# PeripheralExample.net
KiCad netlist of a schematic drawn in EAGLE
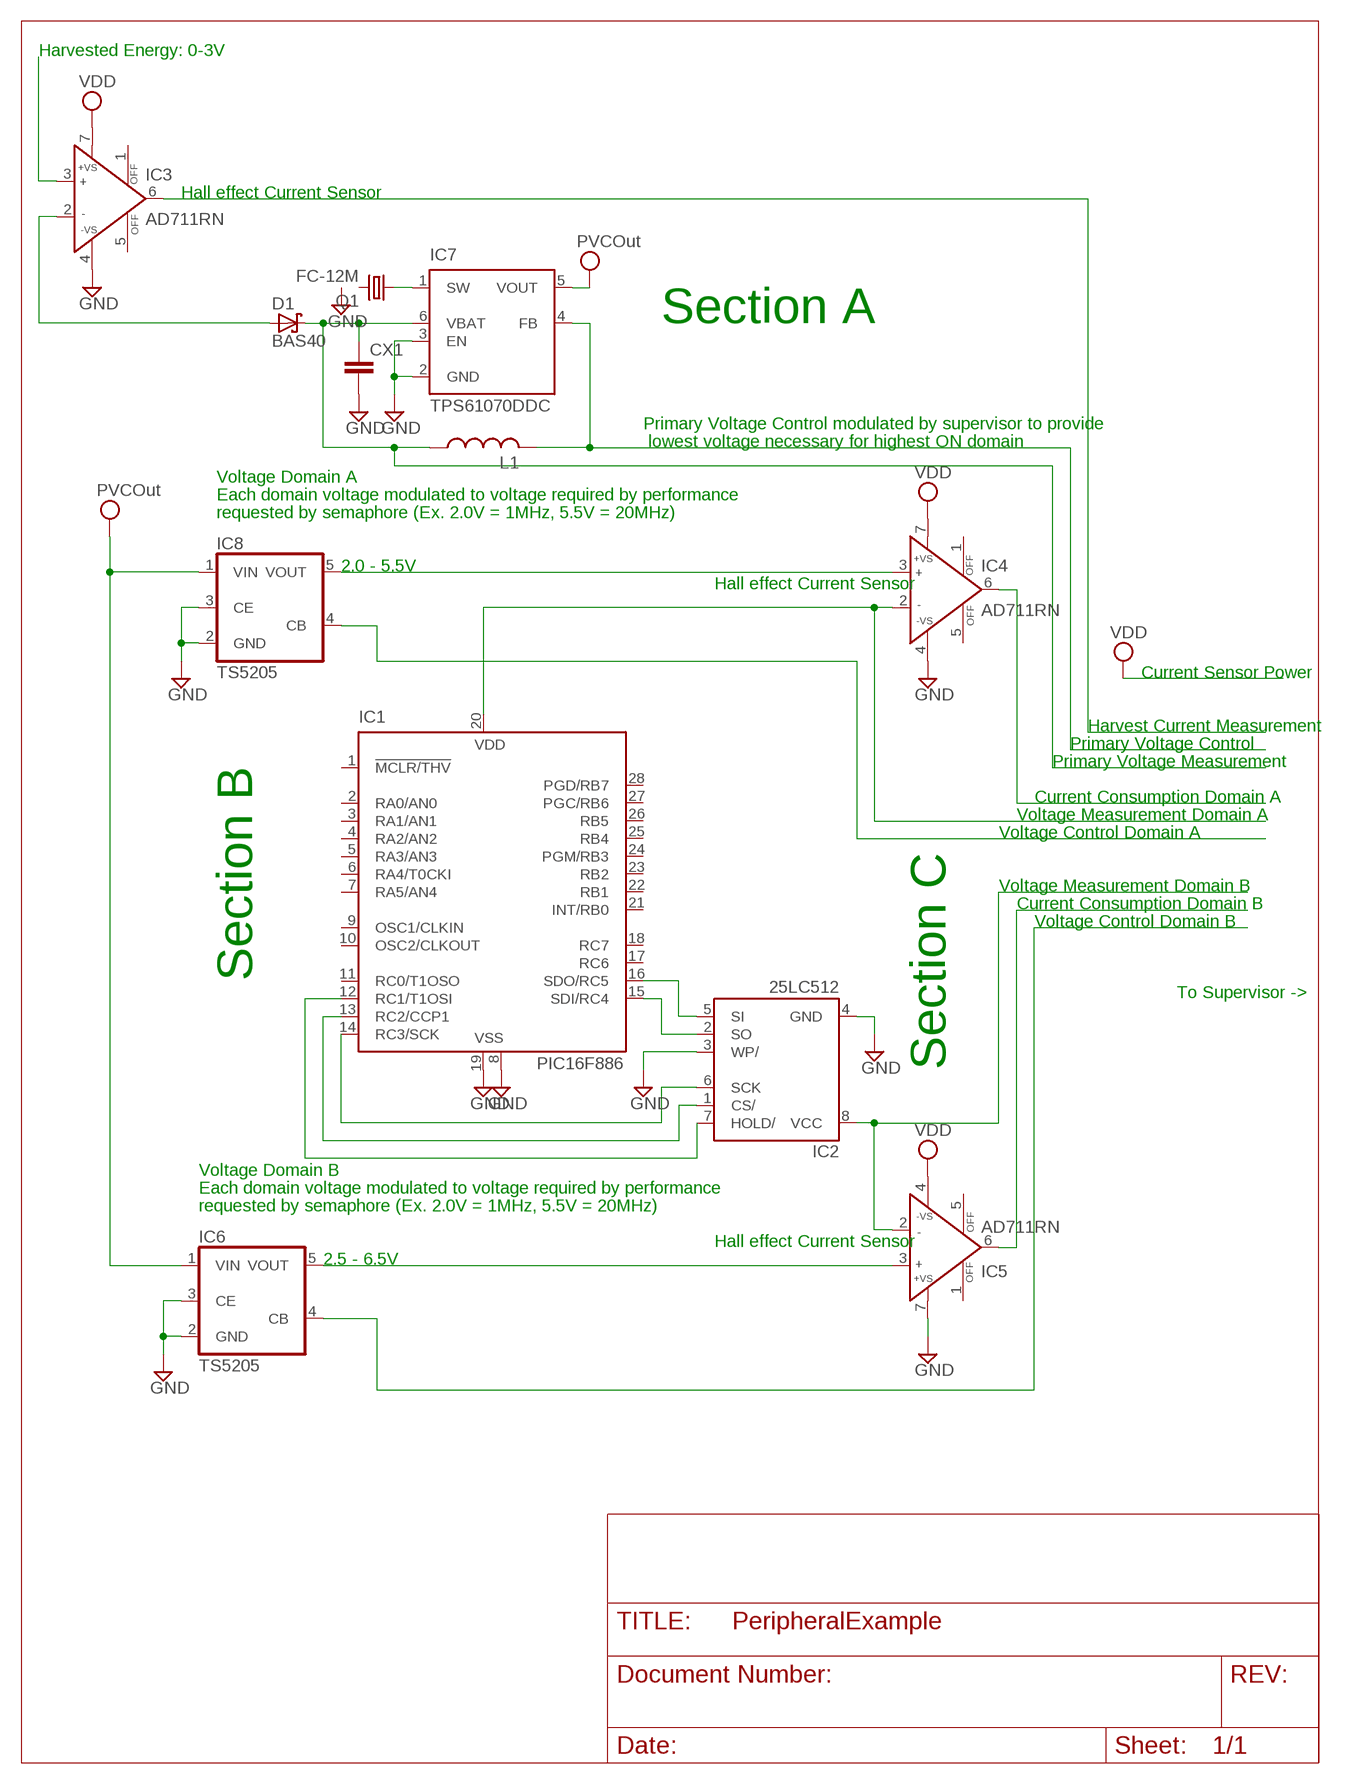
[diagram p0: schematic, sheet 1]

(export (version "E")
  (design (tool "Eeschema 10.0.6"))
  (components
    (comp (ref "CX1")
      (value "CXXC10B5")
      (footprint "eagle-import:XC10B5")
      (libsource (lib "eagle-import") (part "CXXC10B5"))
    )
    (comp (ref "D1")
      (value "BAS40")
      (footprint "eagle-import:SOT23")
      (libsource (lib "eagle-import") (part "BAS40"))
    )
    (comp (ref "IC1")
      (value "PIC16F886")
      (footprint "eagle-import:SO28W")
      (fields (field (name "MF") "MICROCHIP") (field (name "MPN") "PIC16F876-20/SO"))
      (libsource (lib "eagle-import") (part "PIC16876SOF"))
    )
    (comp (ref "IC2")
      (value "25LC512")
      (footprint "eagle-import:DIL08")
      (fields (field (name "MPN") "CAT25040LI-G"))
      (libsource (lib "eagle-import") (part "AT25P"))
    )
    (comp (ref "IC3")
      (value "AD711RN")
      (footprint "eagle-import:SO8")
      (fields (field (name "MF") "ALTERA CORPORATION") (field (name "MPN") "AD711KRZ"))
      (libsource (lib "eagle-import") (part "AD711RN"))
    )
    (comp (ref "IC4")
      (value "AD711RN")
      (footprint "eagle-import:SO8")
      (fields (field (name "MF") "ALTERA CORPORATION") (field (name "MPN") "AD711KRZ"))
      (libsource (lib "eagle-import") (part "AD711RN"))
    )
    (comp (ref "IC5")
      (value "AD711RN")
      (footprint "eagle-import:SO8")
      (fields (field (name "MF") "ALTERA CORPORATION") (field (name "MPN") "AD711KRZ"))
      (libsource (lib "eagle-import") (part "AD711RN"))
    )
    (comp (ref "IC6")
      (value "TS5205")
      (footprint "eagle-import:SOT25")
      (libsource (lib "eagle-import") (part "TS5205"))
    )
    (comp (ref "IC7")
      (value "TPS61070DDC")
      (footprint "eagle-import:TSOT23-6_DDC")
      (fields (field (name "MPN") "TPS61070DDCR"))
      (libsource (lib "eagle-import") (part "TPS6107DDC0"))
    )
    (comp (ref "IC8")
      (value "TS5205")
      (footprint "eagle-import:SOT25")
      (libsource (lib "eagle-import") (part "TS5205"))
    )
    (comp (ref "L1")
      (value "L-USLAP02KR")
      (footprint "eagle-import:LAP02KR")
      (libsource (lib "eagle-import") (part "L-USLAP02KR"))
    )
    (comp (ref "Q1")
      (value "FC-12M")
      (footprint "eagle-import:FC-12M")
      (libsource (lib "eagle-import") (part "FC-12M"))
    )
  )
  (nets
    (net (code "1") (name "GND") (class "Default")
      (node (ref "CX1") (pin "2") (pinfunction "2_2") (pintype "passive"))
      (node (ref "IC1") (pin "19") (pinfunction "VSS_19") (pintype "power_in"))
      (node (ref "IC1") (pin "8") (pinfunction "VSS_8") (pintype "power_in"))
      (node (ref "IC2") (pin "3") (pinfunction "WP/_3") (pintype "input"))
      (node (ref "IC2") (pin "4") (pinfunction "GND_4") (pintype "power_in"))
      (node (ref "IC3") (pin "4") (pinfunction "-VS_4") (pintype "input"))
      (node (ref "IC4") (pin "4") (pinfunction "-VS_4") (pintype "input"))
      (node (ref "IC5") (pin "7") (pinfunction "+VS_7") (pintype "input"))
      (node (ref "IC6") (pin "2") (pinfunction "GND_2") (pintype "passive"))
      (node (ref "IC6") (pin "3") (pinfunction "CE_3") (pintype "input"))
      (node (ref "IC7") (pin "2") (pinfunction "GND_2") (pintype "power_in"))
      (node (ref "IC7") (pin "3") (pinfunction "EN_3") (pintype "input"))
      (node (ref "IC8") (pin "2") (pinfunction "GND_2") (pintype "passive"))
      (node (ref "IC8") (pin "3") (pinfunction "CE_3") (pintype "input"))
    )
    (net (code "2") (name "Net-(D1-A)") (class "Default")
      (node (ref "D1") (pin "1") (pinfunction "A_1") (pintype "passive"))
      (node (ref "IC3") (pin "2") (pinfunction "IN-_2") (pintype "input"))
    )
    (net (code "3") (name "Net-(D1-C)") (class "Default")
      (node (ref "CX1") (pin "1") (pinfunction "1_1") (pintype "passive"))
      (node (ref "D1") (pin "3") (pinfunction "C_3") (pintype "passive"))
      (node (ref "IC7") (pin "6") (pinfunction "VBAT_6") (pintype "input"))
      (node (ref "L1") (pin "1") (pinfunction "1_1") (pintype "passive"))
    )
    (net (code "4") (name "Net-(IC1-RC1{slash}T1OSI)") (class "Default")
      (node (ref "IC1") (pin "12") (pinfunction "RC1/T1OSI_12") (pintype "bidirectional"))
      (node (ref "IC2") (pin "7") (pinfunction "HOLD/_7") (pintype "input"))
    )
    (net (code "5") (name "Net-(IC1-RC2{slash}CCP1)") (class "Default")
      (node (ref "IC1") (pin "13") (pinfunction "RC2/CCP1_13") (pintype "bidirectional"))
      (node (ref "IC2") (pin "1") (pinfunction "CS/_1") (pintype "input"))
    )
    (net (code "6") (name "Net-(IC1-RC3{slash}SCK)") (class "Default")
      (node (ref "IC1") (pin "14") (pinfunction "RC3/SCK_14") (pintype "bidirectional"))
      (node (ref "IC2") (pin "6") (pinfunction "SCK_6") (pintype "bidirectional"))
    )
    (net (code "7") (name "Net-(IC1-SDI{slash}RC4)") (class "Default")
      (node (ref "IC1") (pin "15") (pinfunction "SDI/RC4_15") (pintype "bidirectional"))
      (node (ref "IC2") (pin "2") (pinfunction "SO_2") (pintype "input"))
    )
    (net (code "8") (name "Net-(IC1-SDO{slash}RC5)") (class "Default")
      (node (ref "IC1") (pin "16") (pinfunction "SDO/RC5_16") (pintype "bidirectional"))
      (node (ref "IC2") (pin "5") (pinfunction "SI_5") (pintype "bidirectional"))
    )
    (net (code "9") (name "Net-(IC1-VDD)") (class "Default")
      (node (ref "IC1") (pin "20") (pinfunction "VDD_20") (pintype "power_in"))
      (node (ref "IC4") (pin "2") (pinfunction "IN-_2") (pintype "input"))
    )
    (net (code "10") (name "Net-(IC2-VCC)") (class "Default")
      (node (ref "IC2") (pin "8") (pinfunction "VCC_8") (pintype "power_in"))
      (node (ref "IC5") (pin "2") (pinfunction "IN-_2") (pintype "input"))
    )
    (net (code "11") (name "Net-(IC4-IN+)") (class "Default")
      (node (ref "IC4") (pin "3") (pinfunction "IN+_3") (pintype "input"))
      (node (ref "IC8") (pin "5") (pinfunction "VOUT_5") (pintype "passive"))
    )
    (net (code "12") (name "Net-(IC5-IN+)") (class "Default")
      (node (ref "IC5") (pin "3") (pinfunction "IN+_3") (pintype "input"))
      (node (ref "IC6") (pin "5") (pinfunction "VOUT_5") (pintype "passive"))
    )
    (net (code "13") (name "Net-(IC7-FB)") (class "Default")
      (node (ref "IC7") (pin "4") (pinfunction "FB_4") (pintype "input"))
      (node (ref "L1") (pin "2") (pinfunction "2_2") (pintype "passive"))
    )
    (net (code "14") (name "Net-(IC7-SW)") (class "Default")
      (node (ref "IC7") (pin "1") (pinfunction "SW_1") (pintype "input"))
      (node (ref "Q1") (pin "1") (pinfunction "1_1") (pintype "passive"))
    )
    (net (code "15") (name "PVCOut") (class "Default")
      (node (ref "IC3") (pin "7") (pinfunction "+VS_7") (pintype "input"))
      (node (ref "IC4") (pin "7") (pinfunction "+VS_7") (pintype "input"))
      (node (ref "IC5") (pin "4") (pinfunction "-VS_4") (pintype "input"))
      (node (ref "IC6") (pin "1") (pinfunction "VIN_1") (pintype "input"))
      (node (ref "IC7") (pin "5") (pinfunction "VOUT_5") (pintype "passive"))
      (node (ref "IC8") (pin "1") (pinfunction "VIN_1") (pintype "input"))
    )
    (net (code "16") (name "unconnected-(IC1-INT{slash}RB0-Pad21)") (class "Default")
      (node (ref "IC1") (pin "21") (pinfunction "INT/RB0_21") (pintype "bidirectional"))
    )
    (net (code "17") (name "unconnected-(IC1-OSC1{slash}CLKIN-Pad9)") (class "Default")
      (node (ref "IC1") (pin "9") (pinfunction "OSC1/CLKIN_9") (pintype "input"))
    )
    (net (code "18") (name "unconnected-(IC1-OSC2{slash}CLKOUT-Pad10)") (class "Default")
      (node (ref "IC1") (pin "10") (pinfunction "OSC2/CLKOUT_10") (pintype "output"))
    )
    (net (code "19") (name "unconnected-(IC1-PGC{slash}RB6-Pad27)") (class "Default")
      (node (ref "IC1") (pin "27") (pinfunction "PGC/RB6_27") (pintype "bidirectional"))
    )
    (net (code "20") (name "unconnected-(IC1-PGD{slash}RB7-Pad28)") (class "Default")
      (node (ref "IC1") (pin "28") (pinfunction "PGD/RB7_28") (pintype "bidirectional"))
    )
    (net (code "21") (name "unconnected-(IC1-PGM{slash}RB3-Pad24)") (class "Default")
      (node (ref "IC1") (pin "24") (pinfunction "PGM/RB3_24") (pintype "bidirectional"))
    )
    (net (code "22") (name "unconnected-(IC1-RA0{slash}AN0-Pad2)") (class "Default")
      (node (ref "IC1") (pin "2") (pinfunction "RA0/AN0_2") (pintype "bidirectional"))
    )
    (net (code "23") (name "unconnected-(IC1-RA1{slash}AN1-Pad3)") (class "Default")
      (node (ref "IC1") (pin "3") (pinfunction "RA1/AN1_3") (pintype "bidirectional"))
    )
    (net (code "24") (name "unconnected-(IC1-RA2{slash}AN2-Pad4)") (class "Default")
      (node (ref "IC1") (pin "4") (pinfunction "RA2/AN2_4") (pintype "bidirectional"))
    )
    (net (code "25") (name "unconnected-(IC1-RA3{slash}AN3-Pad5)") (class "Default")
      (node (ref "IC1") (pin "5") (pinfunction "RA3/AN3_5") (pintype "bidirectional"))
    )
    (net (code "26") (name "unconnected-(IC1-RA4{slash}T0CKI-Pad6)") (class "Default")
      (node (ref "IC1") (pin "6") (pinfunction "RA4/T0CKI_6") (pintype "bidirectional"))
    )
    (net (code "27") (name "unconnected-(IC1-RA5{slash}AN4-Pad7)") (class "Default")
      (node (ref "IC1") (pin "7") (pinfunction "RA5/AN4_7") (pintype "bidirectional"))
    )
    (net (code "28") (name "unconnected-(IC1-RB1-Pad22)") (class "Default")
      (node (ref "IC1") (pin "22") (pinfunction "RB1_22") (pintype "bidirectional"))
    )
    (net (code "29") (name "unconnected-(IC1-RB2-Pad23)") (class "Default")
      (node (ref "IC1") (pin "23") (pinfunction "RB2_23") (pintype "bidirectional"))
    )
    (net (code "30") (name "unconnected-(IC1-RB4-Pad25)") (class "Default")
      (node (ref "IC1") (pin "25") (pinfunction "RB4_25") (pintype "bidirectional"))
    )
    (net (code "31") (name "unconnected-(IC1-RB5-Pad26)") (class "Default")
      (node (ref "IC1") (pin "26") (pinfunction "RB5_26") (pintype "bidirectional"))
    )
    (net (code "32") (name "unconnected-(IC1-RC0{slash}T1OSO-Pad11)") (class "Default")
      (node (ref "IC1") (pin "11") (pinfunction "RC0/T1OSO_11") (pintype "bidirectional"))
    )
    (net (code "33") (name "unconnected-(IC1-RC6-Pad17)") (class "Default")
      (node (ref "IC1") (pin "17") (pinfunction "RC6_17") (pintype "bidirectional"))
    )
    (net (code "34") (name "unconnected-(IC1-RC7-Pad18)") (class "Default")
      (node (ref "IC1") (pin "18") (pinfunction "RC7_18") (pintype "bidirectional"))
    )
    (net (code "35") (name "unconnected-(IC1-~{MCLR{slash}THV}-Pad1)") (class "Default")
      (node (ref "IC1") (pin "1") (pinfunction "~{MCLR/THV}_1") (pintype "input"))
    )
    (net (code "36") (name "unconnected-(IC3-IN+-Pad3)") (class "Default")
      (node (ref "IC3") (pin "3") (pinfunction "IN+_3") (pintype "input"))
    )
    (net (code "37") (name "unconnected-(IC3-OFF-Pad1)") (class "Default")
      (node (ref "IC3") (pin "1") (pinfunction "OFF_1") (pintype "passive"))
    )
    (net (code "38") (name "unconnected-(IC3-OFF-Pad5)") (class "Default")
      (node (ref "IC3") (pin "5") (pinfunction "OFF_5") (pintype "passive"))
    )
    (net (code "39") (name "unconnected-(IC3-OUT-Pad6)") (class "Default")
      (node (ref "IC3") (pin "6") (pinfunction "OUT_6") (pintype "output"))
    )
    (net (code "40") (name "unconnected-(IC4-OFF-Pad1)") (class "Default")
      (node (ref "IC4") (pin "1") (pinfunction "OFF_1") (pintype "passive"))
    )
    (net (code "41") (name "unconnected-(IC4-OFF-Pad5)") (class "Default")
      (node (ref "IC4") (pin "5") (pinfunction "OFF_5") (pintype "passive"))
    )
    (net (code "42") (name "unconnected-(IC4-OUT-Pad6)") (class "Default")
      (node (ref "IC4") (pin "6") (pinfunction "OUT_6") (pintype "output"))
    )
    (net (code "43") (name "unconnected-(IC5-OFF-Pad1)") (class "Default")
      (node (ref "IC5") (pin "1") (pinfunction "OFF_1") (pintype "passive"))
    )
    (net (code "44") (name "unconnected-(IC5-OFF-Pad5)") (class "Default")
      (node (ref "IC5") (pin "5") (pinfunction "OFF_5") (pintype "passive"))
    )
    (net (code "45") (name "unconnected-(IC5-OUT-Pad6)") (class "Default")
      (node (ref "IC5") (pin "6") (pinfunction "OUT_6") (pintype "output"))
    )
    (net (code "46") (name "unconnected-(IC6-CB-Pad4)") (class "Default")
      (node (ref "IC6") (pin "4") (pinfunction "CB_4") (pintype "input"))
    )
    (net (code "47") (name "unconnected-(IC8-CB-Pad4)") (class "Default")
      (node (ref "IC8") (pin "4") (pinfunction "CB_4") (pintype "input"))
    )
    (net (code "48") (name "unconnected-(Q1-Pad2)") (class "Default")
      (node (ref "Q1") (pin "2") (pinfunction "2_2") (pintype "passive"))
    )
  )
)
